# eeArm_Breakout.net
KiCad netlist of a schematic drawn in EAGLE
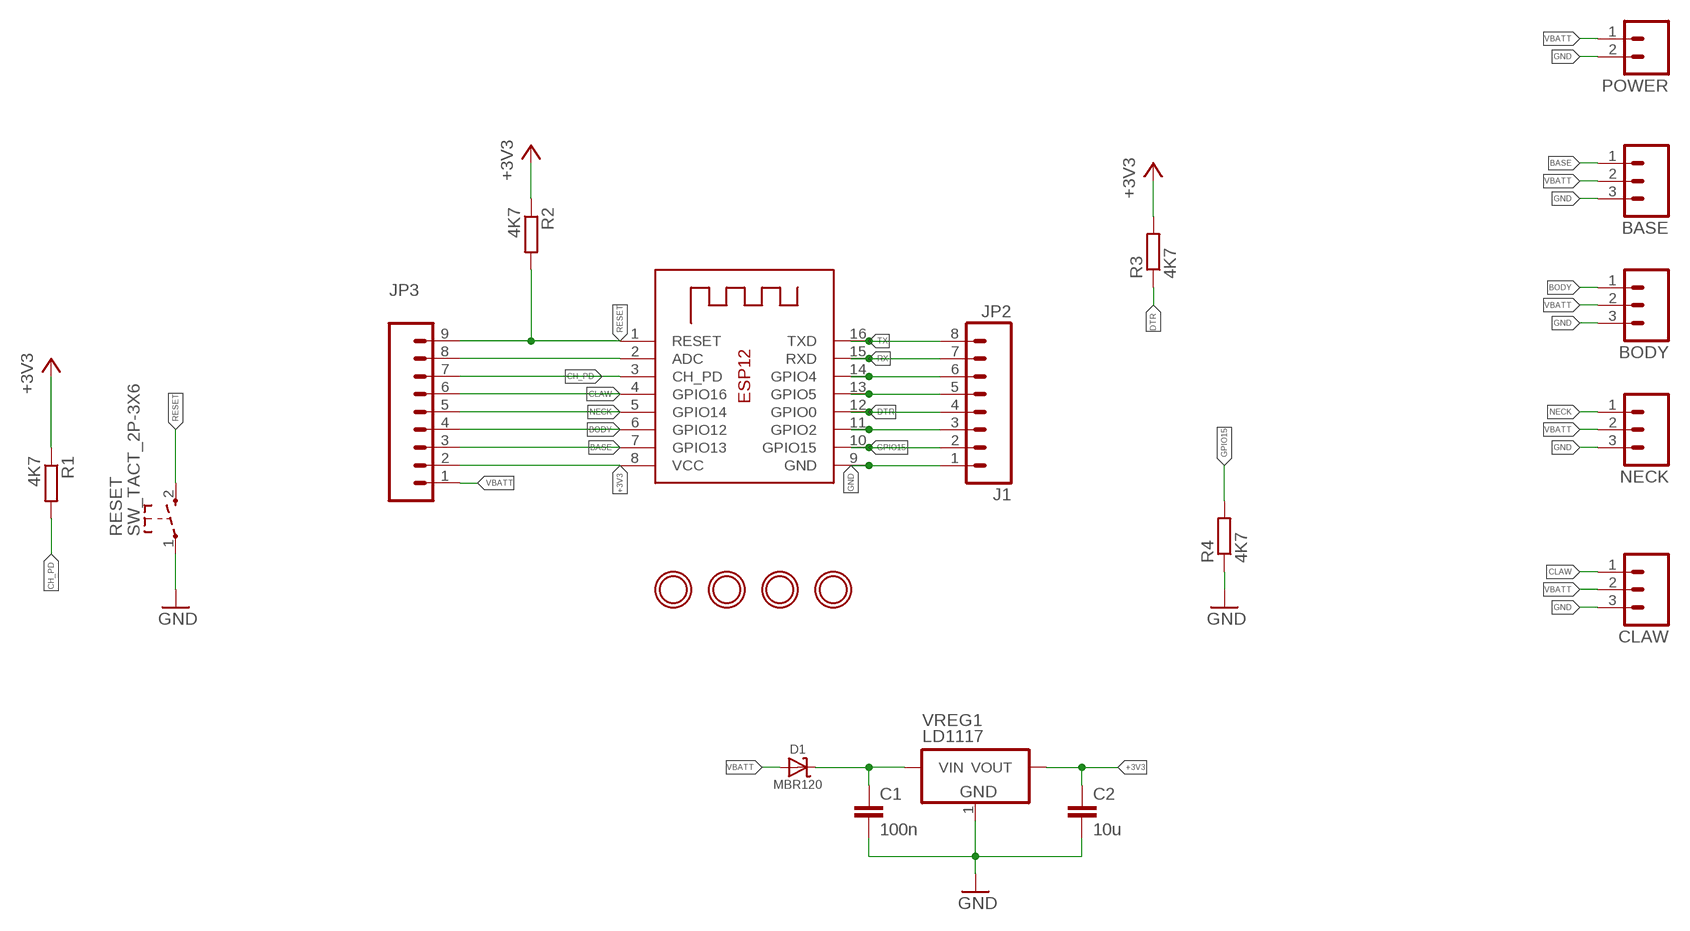
[diagram p0: schematic, sheet 1]

(export (version "E")
  (design (tool "Eeschema 10.0.6"))
  (components
    (comp (ref "BASE")
      (value "M03LOCK")
      (footprint "eagle-import:1X03_LOCK")
      (libsource (lib "eagle-import") (part "M03LOCK"))
    )
    (comp (ref "BODY")
      (value "M03LOCK")
      (footprint "eagle-import:1X03_LOCK")
      (libsource (lib "eagle-import") (part "M03LOCK"))
    )
    (comp (ref "C1")
      (value "100n")
      (footprint "eagle-import:C0805")
      (libsource (lib "eagle-import") (part "C-EUC0805"))
    )
    (comp (ref "C2")
      (value "10u")
      (footprint "eagle-import:C0805")
      (libsource (lib "eagle-import") (part "C-EUC0805"))
    )
    (comp (ref "CLAW")
      (value "M03LOCK")
      (footprint "eagle-import:1X03_LOCK")
      (libsource (lib "eagle-import") (part "M03LOCK"))
    )
    (comp (ref "D1")
      (value "MBR120")
      (footprint "eagle-import:SOD-123")
      (libsource (lib "eagle-import") (part "DIODE-SCHOTTKYSOD-123"))
    )
    (comp (ref "JP2")
      (value "J1")
      (footprint "eagle-import:1X08_LOCK")
      (libsource (lib "eagle-import") (part "M08LOCK"))
    )
    (comp (ref "JP3")
      (value "M09LOCK")
      (footprint "eagle-import:1X09_LOCK")
      (libsource (lib "eagle-import") (part "M09LOCK"))
    )
    (comp (ref "NECK")
      (value "M03LOCK")
      (footprint "eagle-import:1X03_LOCK")
      (libsource (lib "eagle-import") (part "M03LOCK"))
    )
    (comp (ref "POWER")
      (value "M02LOCK")
      (footprint "eagle-import:1X02_LOCK")
      (libsource (lib "eagle-import") (part "M02LOCK"))
    )
    (comp (ref "R1")
      (value "4K7")
      (footprint "eagle-import:R0805")
      (libsource (lib "eagle-import") (part "R-EU_R0805"))
    )
    (comp (ref "R2")
      (value "4K7")
      (footprint "eagle-import:R0805")
      (libsource (lib "eagle-import") (part "R-EU_R0805"))
    )
    (comp (ref "R3")
      (value "4K7")
      (footprint "eagle-import:R0805")
      (libsource (lib "eagle-import") (part "R-EU_R0805"))
    )
    (comp (ref "R4")
      (value "4K7")
      (footprint "eagle-import:R0805")
      (libsource (lib "eagle-import") (part "R-EU_R0805"))
    )
    (comp (ref "RESET")
      (value "SW_TACT_2P-3X6")
      (footprint "eagle-import:SW_TACT_3X6")
      (libsource (lib "eagle-import") (part "SW_TACT_2P-3X6"))
    )
    (comp (ref "U$6")
      (value "MOUNTINGHOLE2.0")
      (footprint "eagle-import:MOUNTINGHOLE_2.0_PLATED")
      (libsource (lib "eagle-import") (part "MOUNTINGHOLE2.0"))
    )
    (comp (ref "U$7")
      (value "MOUNTINGHOLE2.0")
      (footprint "eagle-import:MOUNTINGHOLE_2.0_PLATED")
      (libsource (lib "eagle-import") (part "MOUNTINGHOLE2.0"))
    )
    (comp (ref "U$8")
      (value "MOUNTINGHOLE2.0")
      (footprint "eagle-import:MOUNTINGHOLE_2.0_PLATED")
      (libsource (lib "eagle-import") (part "MOUNTINGHOLE2.0"))
    )
    (comp (ref "U$9")
      (value "MOUNTINGHOLE2.0")
      (footprint "eagle-import:MOUNTINGHOLE_2.0_PLATED")
      (libsource (lib "eagle-import") (part "MOUNTINGHOLE2.0"))
    )
    (comp (ref "VREG1")
      (value "LD1117")
      (footprint "eagle-import:SOT-223")
      (libsource (lib "eagle-import") (part "VREG_3PINS-SOT-223"))
    )
    (comp (ref "X1")
      (value "ESP8266")
      (footprint "eagle-import:ESP-12-NOPLACE")
      (libsource (lib "eagle-import") (part "ESP-12X"))
    )
  )
  (nets
    (net (code "1") (name "+3V3") (class "Default")
      (node (ref "C2") (pin "1") (pinfunction "1_1") (pintype "passive"))
      (node (ref "JP3") (pin "2") (pinfunction "2_2") (pintype "passive"))
      (node (ref "R1") (pin "1") (pinfunction "1_1") (pintype "passive"))
      (node (ref "R2") (pin "1") (pinfunction "1_1") (pintype "passive"))
      (node (ref "R3") (pin "2") (pinfunction "2_2") (pintype "passive"))
      (node (ref "VREG1") (pin "2") (pinfunction "VOUT_2") (pintype "bidirectional"))
      (node (ref "X1") (pin "8") (pinfunction "VCC_8") (pintype "power_in"))
    )
    (net (code "2") (name "BASE") (class "Default")
      (node (ref "BASE") (pin "1") (pinfunction "1_1") (pintype "passive"))
      (node (ref "JP3") (pin "3") (pinfunction "3_3") (pintype "passive"))
      (node (ref "X1") (pin "7") (pinfunction "GPIO13_7") (pintype "bidirectional"))
    )
    (net (code "3") (name "BODY") (class "Default")
      (node (ref "BODY") (pin "1") (pinfunction "1_1") (pintype "passive"))
      (node (ref "JP3") (pin "4") (pinfunction "4_4") (pintype "passive"))
      (node (ref "X1") (pin "6") (pinfunction "GPIO12_6") (pintype "bidirectional"))
    )
    (net (code "4") (name "CH_PD") (class "Default")
      (node (ref "JP3") (pin "7") (pinfunction "7_7") (pintype "passive"))
      (node (ref "R1") (pin "2") (pinfunction "2_2") (pintype "passive"))
      (node (ref "X1") (pin "3") (pinfunction "CH_PD_3") (pintype "input"))
    )
    (net (code "5") (name "CLAW") (class "Default")
      (node (ref "CLAW") (pin "1") (pinfunction "1_1") (pintype "passive"))
      (node (ref "JP3") (pin "6") (pinfunction "6_6") (pintype "passive"))
      (node (ref "X1") (pin "4") (pinfunction "GPIO16_4") (pintype "bidirectional"))
    )
    (net (code "6") (name "DTR") (class "Default")
      (node (ref "JP2") (pin "4") (pinfunction "4_4") (pintype "passive"))
      (node (ref "R3") (pin "1") (pinfunction "1_1") (pintype "passive"))
      (node (ref "X1") (pin "12") (pinfunction "GPIO0_12") (pintype "bidirectional"))
    )
    (net (code "7") (name "GND") (class "Default")
      (node (ref "BASE") (pin "3") (pinfunction "3_3") (pintype "passive"))
      (node (ref "BODY") (pin "3") (pinfunction "3_3") (pintype "passive"))
      (node (ref "C1") (pin "2") (pinfunction "2_2") (pintype "passive"))
      (node (ref "C2") (pin "2") (pinfunction "2_2") (pintype "passive"))
      (node (ref "CLAW") (pin "3") (pinfunction "3_3") (pintype "passive"))
      (node (ref "JP2") (pin "1") (pinfunction "1_1") (pintype "passive"))
      (node (ref "NECK") (pin "3") (pinfunction "3_3") (pintype "passive"))
      (node (ref "POWER") (pin "2") (pinfunction "2_2") (pintype "passive"))
      (node (ref "R4") (pin "1") (pinfunction "1_1") (pintype "passive"))
      (node (ref "RESET") (pin "1") (pinfunction "1_1") (pintype "passive"))
      (node (ref "VREG1") (pin "1") (pinfunction "GND_1") (pintype "bidirectional"))
      (node (ref "X1") (pin "9") (pinfunction "GND_9") (pintype "power_in"))
    )
    (net (code "8") (name "GPIO15") (class "Default")
      (node (ref "JP2") (pin "2") (pinfunction "2_2") (pintype "passive"))
      (node (ref "R4") (pin "2") (pinfunction "2_2") (pintype "passive"))
      (node (ref "X1") (pin "10") (pinfunction "GPIO15_10") (pintype "bidirectional"))
    )
    (net (code "9") (name "NECK") (class "Default")
      (node (ref "JP3") (pin "5") (pinfunction "5_5") (pintype "passive"))
      (node (ref "NECK") (pin "1") (pinfunction "1_1") (pintype "passive"))
      (node (ref "X1") (pin "5") (pinfunction "GPIO14_5") (pintype "bidirectional"))
    )
    (net (code "10") (name "Net-(VREG1-VIN)") (class "Default")
      (node (ref "C1") (pin "1") (pinfunction "1_1") (pintype "passive"))
      (node (ref "D1") (pin "C") (pinfunction "C_C") (pintype "passive"))
      (node (ref "VREG1") (pin "3") (pinfunction "VIN_3") (pintype "bidirectional"))
    )
    (net (code "11") (name "Net-(X1-ADC)") (class "Default")
      (node (ref "JP3") (pin "8") (pinfunction "8_8") (pintype "passive"))
      (node (ref "X1") (pin "2") (pinfunction "ADC_2") (pintype "passive"))
    )
    (net (code "12") (name "Net-(X1-GPIO2)") (class "Default")
      (node (ref "JP2") (pin "3") (pinfunction "3_3") (pintype "passive"))
      (node (ref "X1") (pin "11") (pinfunction "GPIO2_11") (pintype "bidirectional"))
    )
    (net (code "13") (name "Net-(X1-GPIO4)") (class "Default")
      (node (ref "JP2") (pin "6") (pinfunction "6_6") (pintype "passive"))
      (node (ref "X1") (pin "14") (pinfunction "GPIO4_14") (pintype "bidirectional"))
    )
    (net (code "14") (name "Net-(X1-GPIO5)") (class "Default")
      (node (ref "JP2") (pin "5") (pinfunction "5_5") (pintype "passive"))
      (node (ref "X1") (pin "13") (pinfunction "GPIO5_13") (pintype "bidirectional"))
    )
    (net (code "15") (name "RESET") (class "Default")
      (node (ref "JP3") (pin "9") (pinfunction "9_9") (pintype "passive"))
      (node (ref "R2") (pin "2") (pinfunction "2_2") (pintype "passive"))
      (node (ref "RESET") (pin "2") (pinfunction "3_2") (pintype "passive"))
      (node (ref "X1") (pin "1") (pinfunction "RESET_1") (pintype "input"))
    )
    (net (code "16") (name "RX") (class "Default")
      (node (ref "JP2") (pin "7") (pinfunction "7_7") (pintype "passive"))
      (node (ref "X1") (pin "15") (pinfunction "RXD_15") (pintype "input"))
    )
    (net (code "17") (name "TX") (class "Default")
      (node (ref "JP2") (pin "8") (pinfunction "8_8") (pintype "passive"))
      (node (ref "X1") (pin "16") (pinfunction "TXD_16") (pintype "output"))
    )
    (net (code "18") (name "VBATT") (class "Default")
      (node (ref "BASE") (pin "2") (pinfunction "2_2") (pintype "passive"))
      (node (ref "BODY") (pin "2") (pinfunction "2_2") (pintype "passive"))
      (node (ref "CLAW") (pin "2") (pinfunction "2_2") (pintype "passive"))
      (node (ref "D1") (pin "A") (pinfunction "A_A") (pintype "passive"))
      (node (ref "JP3") (pin "1") (pinfunction "1_1") (pintype "passive"))
      (node (ref "NECK") (pin "2") (pinfunction "2_2") (pintype "passive"))
      (node (ref "POWER") (pin "1") (pinfunction "1_1") (pintype "passive"))
    )
  )
)
